# ConverterBoardRev2_3.net
KiCad netlist of a schematic drawn in EAGLE
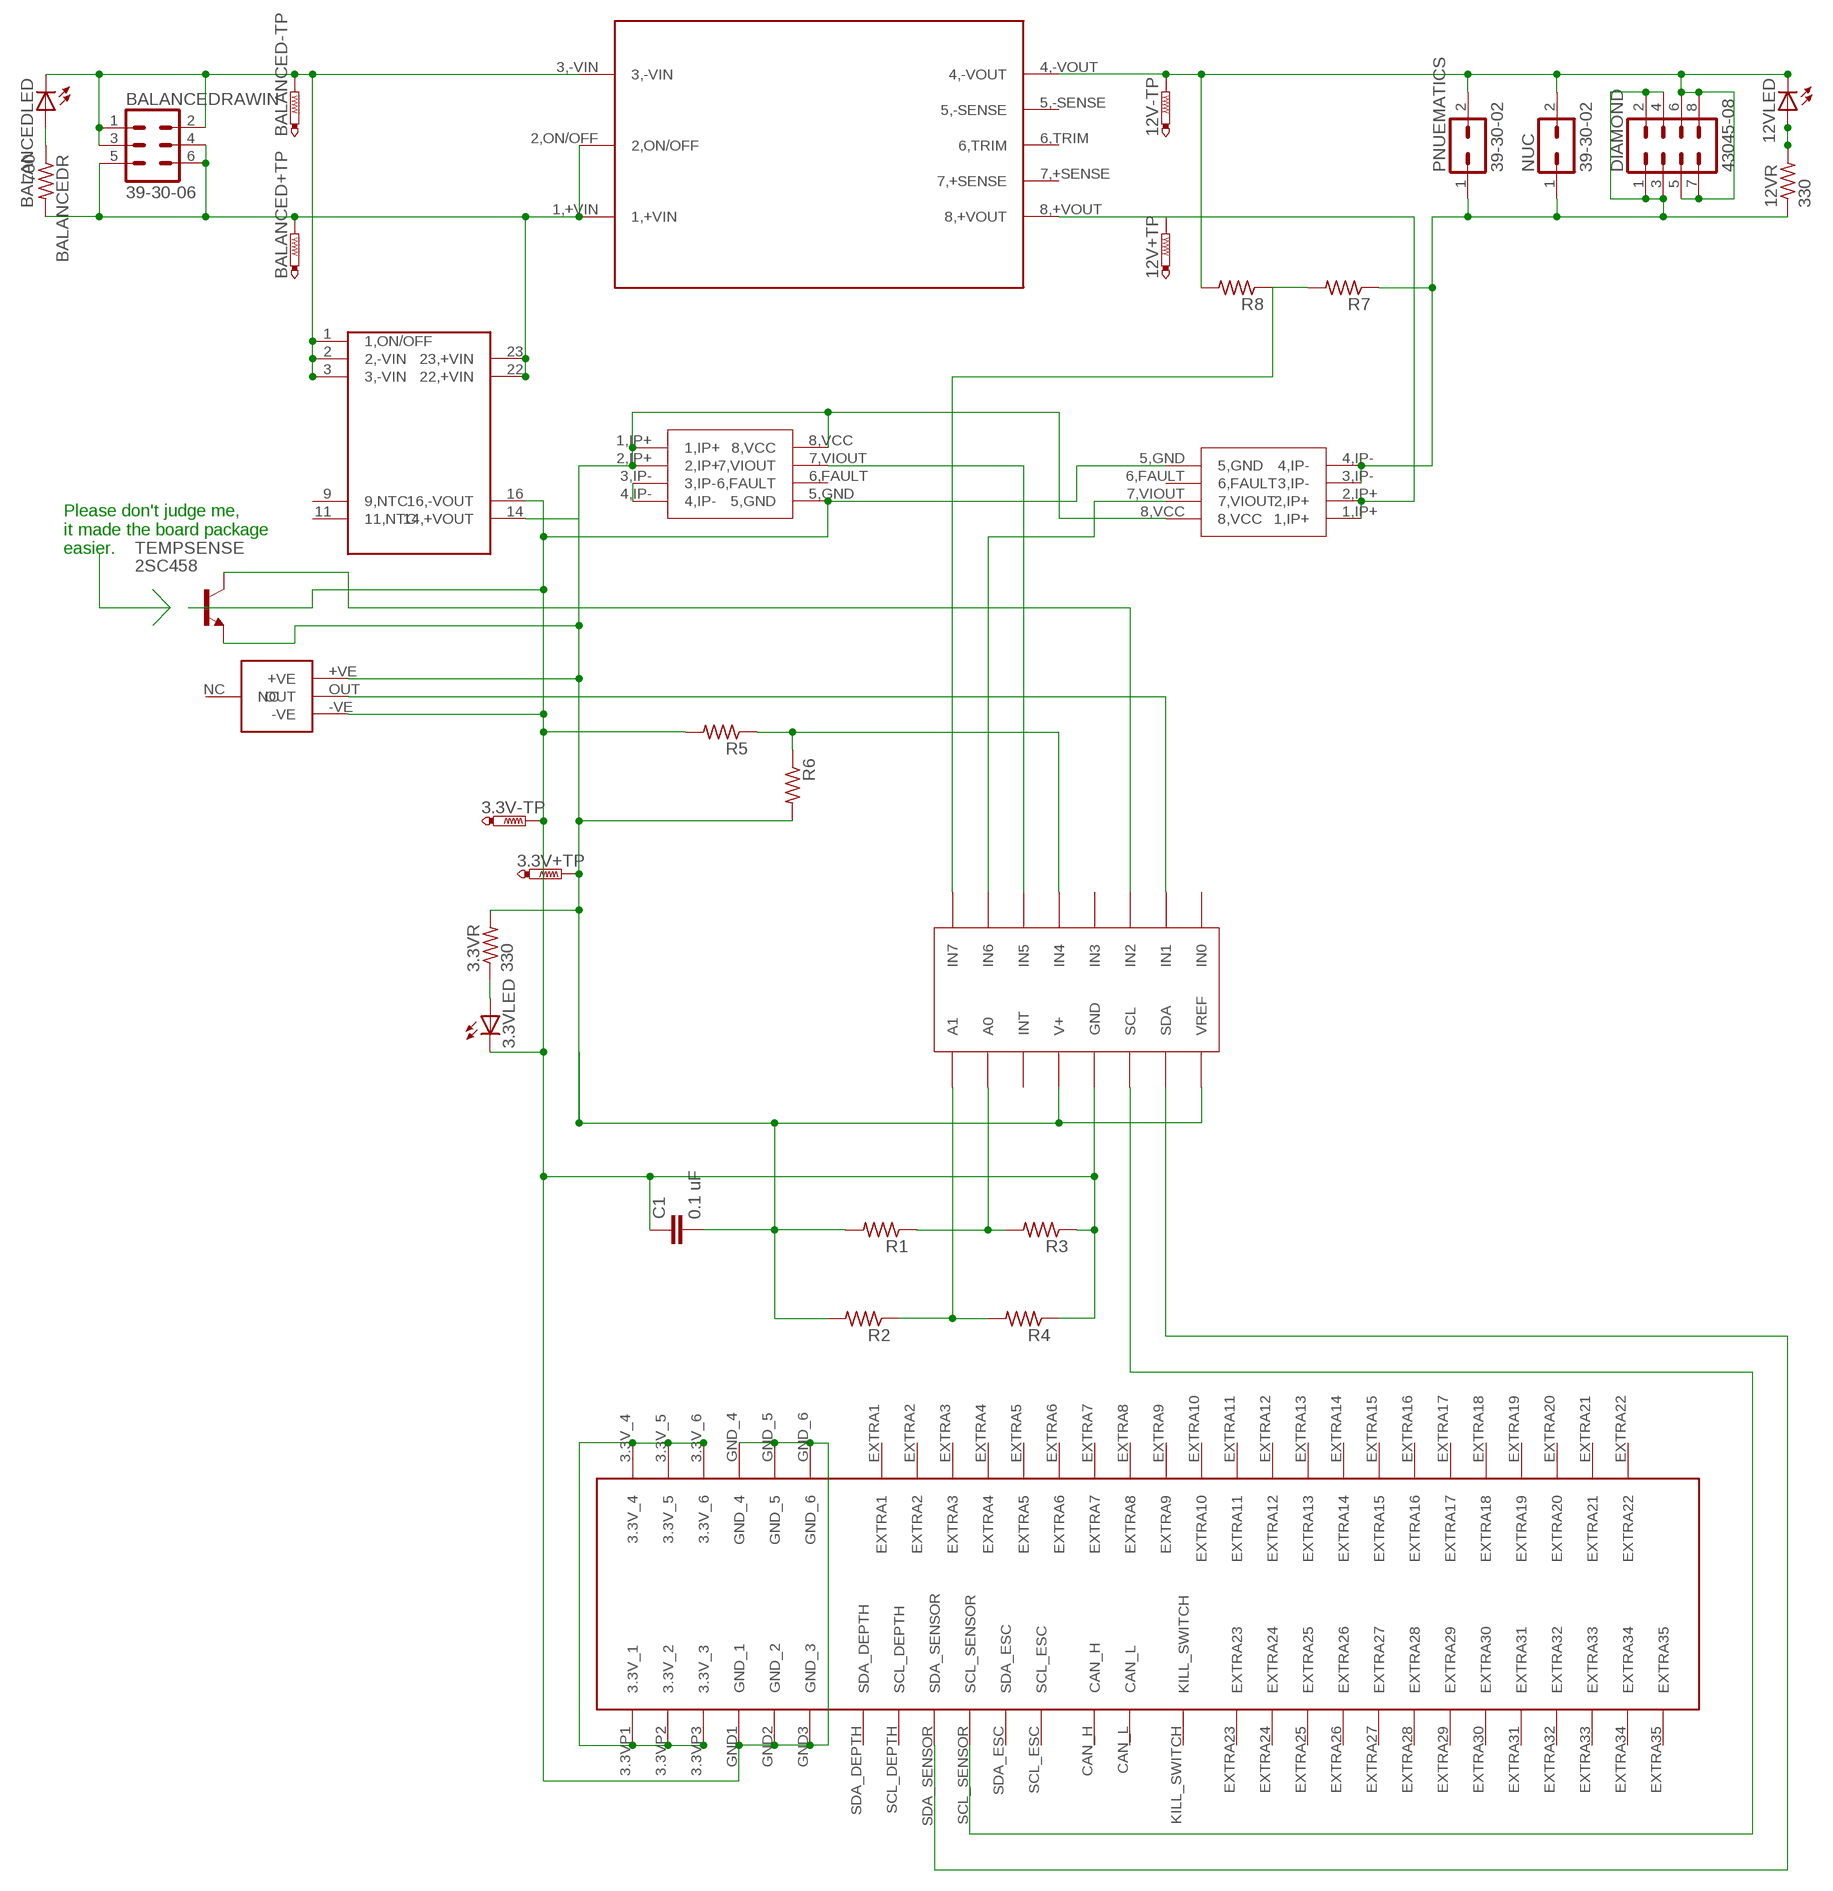
[diagram p0: schematic, sheet 1]

(export (version "E")
  (design (tool "Eeschema 10.0.6"))
  (components
    (comp (ref "3.3V+TP")
      (value "PTR1B1,27")
      (footprint "eagle-import:B1,27")
      (libsource (lib "eagle-import") (part "PTR1B1,27"))
    )
    (comp (ref "3.3V-TP")
      (value "PTR1B1,27")
      (footprint "eagle-import:B1,27")
      (libsource (lib "eagle-import") (part "PTR1B1,27"))
    )
    (comp (ref "3.3VLED")
      (value "LTST-S270GKT")
      (footprint "eagle-import:LTST-S270GKT")
      (libsource (lib "eagle-import") (part "LTST-S270GKT"))
    )
    (comp (ref "3.3VR")
      (value "330")
      (footprint "eagle-import:0204_7")
      (libsource (lib "eagle-import") (part "R-US_0204/7"))
    )
    (comp (ref "3V3CUR")
      (value "CURRENTSENS")
      (footprint "eagle-import:CURRENTSENS")
      (libsource (lib "eagle-import") (part "CURRENTSENS"))
    )
    (comp (ref "12V+TP")
      (value "PTR1B1,27")
      (footprint "eagle-import:B1,27")
      (libsource (lib "eagle-import") (part "PTR1B1,27"))
    )
    (comp (ref "12V-TP")
      (value "PTR1B1,27")
      (footprint "eagle-import:B1,27")
      (libsource (lib "eagle-import") (part "PTR1B1,27"))
    )
    (comp (ref "12VCUR")
      (value "CURRENTSENS")
      (footprint "eagle-import:CURRENTSENS")
      (libsource (lib "eagle-import") (part "CURRENTSENS"))
    )
    (comp (ref "12VLED")
      (value "LTST-S270GKT")
      (footprint "eagle-import:LTST-S270GKT")
      (libsource (lib "eagle-import") (part "LTST-S270GKT"))
    )
    (comp (ref "12VR")
      (value "330")
      (footprint "eagle-import:0204_7")
      (libsource (lib "eagle-import") (part "R-US_0204/7"))
    )
    (comp (ref "BALANCED+TP")
      (value "PTR1B1,27")
      (footprint "eagle-import:B1,27")
      (libsource (lib "eagle-import") (part "PTR1B1,27"))
    )
    (comp (ref "BALANCED-TP")
      (value "PTR1B1,27")
      (footprint "eagle-import:B1,27")
      (libsource (lib "eagle-import") (part "PTR1B1,27"))
    )
    (comp (ref "BALANCEDLED")
      (value "LTST-S270GKT")
      (footprint "eagle-import:LTST-S270GKT")
      (libsource (lib "eagle-import") (part "LTST-S270GKT"))
    )
    (comp (ref "BALANCEDR")
      (value "700")
      (footprint "eagle-import:0204_7")
      (libsource (lib "eagle-import") (part "R-US_0204/7"))
    )
    (comp (ref "BALANCEDRAWIN")
      (value "39-30-06")
      (footprint "eagle-import:39-30-_06_")
      (libsource (lib "eagle-import") (part "39-30-?06?"))
    )
    (comp (ref "C1")
      (value "0.1 uF")
      (footprint "eagle-import:C025-024X044")
      (libsource (lib "eagle-import") (part "C-EU025-024X044"))
    )
    (comp (ref "DIAMOND")
      (value "43045-08")
      (footprint "eagle-import:43045-08")
      (libsource (lib "eagle-import") (part "43045-08"))
    )
    (comp (ref "NUC")
      (value "39-30-02")
      (footprint "eagle-import:39-30-_02_")
      (libsource (lib "eagle-import") (part "39-30-?02?"))
    )
    (comp (ref "PNUEMATICS")
      (value "39-30-02")
      (footprint "eagle-import:39-30-_02_")
      (libsource (lib "eagle-import") (part "39-30-?02?"))
    )
    (comp (ref "R1")
      (value "R-US_0204/7")
      (footprint "eagle-import:0204_7")
      (libsource (lib "eagle-import") (part "R-US_0204/7"))
    )
    (comp (ref "R2")
      (value "R-US_0204/7")
      (footprint "eagle-import:0204_7")
      (libsource (lib "eagle-import") (part "R-US_0204/7"))
    )
    (comp (ref "R3")
      (value "R-US_0204/7")
      (footprint "eagle-import:0204_7")
      (libsource (lib "eagle-import") (part "R-US_0204/7"))
    )
    (comp (ref "R4")
      (value "R-US_0204/7")
      (footprint "eagle-import:0204_7")
      (libsource (lib "eagle-import") (part "R-US_0204/7"))
    )
    (comp (ref "R5")
      (value "R-US_0204/7")
      (footprint "eagle-import:0204_7")
      (libsource (lib "eagle-import") (part "R-US_0204/7"))
    )
    (comp (ref "R6")
      (value "R-US_0204/7")
      (footprint "eagle-import:0204_7")
      (libsource (lib "eagle-import") (part "R-US_0204/7"))
    )
    (comp (ref "R7")
      (value "R-US_0204/7")
      (footprint "eagle-import:0204_7")
      (libsource (lib "eagle-import") (part "R-US_0204/7"))
    )
    (comp (ref "R8")
      (value "R-US_0204/7")
      (footprint "eagle-import:0204_7")
      (libsource (lib "eagle-import") (part "R-US_0204/7"))
    )
    (comp (ref "TEMPSENSE")
      (value "2SC458")
      (footprint "eagle-import:TO92-ECB")
      (libsource (lib "eagle-import") (part "2SC458"))
    )
    (comp (ref "U$1")
      (value "12VCONV")
      (footprint "eagle-import:12VCONV")
      (libsource (lib "eagle-import") (part "12VCONV"))
    )
    (comp (ref "U$2")
      (value "3.3VCONV")
      (footprint "eagle-import:3.3VCONV")
      (libsource (lib "eagle-import") (part "3.3VCONV"))
    )
    (comp (ref "U$3")
      (value "5530843")
      (footprint "eagle-import:5530843-6-BOARDFINGERS")
      (libsource (lib "eagle-import") (part "5530843"))
    )
    (comp (ref "U$6")
      (value "HUMIDITYSENSOR")
      (footprint "eagle-import:HUMIDITYSENSOR")
      (libsource (lib "eagle-import") (part "HUMIDITYSENSOR"))
    )
    (comp (ref "U$8")
      (value "ADC128D818")
      (footprint "eagle-import:TSSOP-16")
      (libsource (lib "eagle-import") (part "ADC128D818"))
    )
  )
  (nets
    (net (code "1") (name "/3.3VBKPLN") (class "Default")
      (node (ref "3V3CUR") (pin "3,IP-") (pinfunction "3,IP-_3,IP-") (pintype "bidirectional"))
      (node (ref "3V3CUR") (pin "4,IP-") (pinfunction "4,IP-_4,IP-") (pintype "bidirectional"))
      (node (ref "U$3") (pin "3.3VP1") (pinfunction "3.3V_1_3.3VP1") (pintype "bidirectional"))
      (node (ref "U$3") (pin "3.3VP2") (pinfunction "3.3V_2_3.3VP2") (pintype "bidirectional"))
      (node (ref "U$3") (pin "3.3VP3") (pinfunction "3.3V_3_3.3VP3") (pintype "bidirectional"))
      (node (ref "U$3") (pin "3.3V_4") (pinfunction "3.3V_4_3.3V_4") (pintype "bidirectional"))
      (node (ref "U$3") (pin "3.3V_5") (pinfunction "3.3V_5_3.3V_5") (pintype "bidirectional"))
      (node (ref "U$3") (pin "3.3V_6") (pinfunction "3.3V_6_3.3V_6") (pintype "bidirectional"))
    )
    (net (code "2") (name "Net-(3.3VLED-A)") (class "Default")
      (node (ref "3.3VLED") (pin "ANODE") (pinfunction "A_ANODE") (pintype "passive"))
      (node (ref "3.3VR") (pin "1") (pinfunction "1_1") (pintype "passive"))
    )
    (net (code "3") (name "Net-(3.3VLED-C)") (class "Default")
      (node (ref "12VCUR") (pin "5,GND") (pinfunction "5,GND_5,GND") (pintype "bidirectional"))
      (node (ref "3.3V-TP") (pin "TP") (pinfunction "TP_TP") (pintype "input"))
      (node (ref "3.3VLED") (pin "CATHODE") (pinfunction "C_CATHODE") (pintype "passive"))
      (node (ref "3V3CUR") (pin "5,GND") (pinfunction "5,GND_5,GND") (pintype "bidirectional"))
      (node (ref "C1") (pin "1") (pinfunction "1_1") (pintype "passive"))
      (node (ref "R3") (pin "1") (pinfunction "1_1") (pintype "passive"))
      (node (ref "R4") (pin "1") (pinfunction "1_1") (pintype "passive"))
      (node (ref "R5") (pin "2") (pinfunction "2_2") (pintype "passive"))
      (node (ref "TEMPSENSE") (pin "B") (pinfunction "B_B") (pintype "passive"))
      (node (ref "U$2") (pin "16") (pinfunction "16,-VOUT_16") (pintype "bidirectional"))
      (node (ref "U$3") (pin "GND1") (pinfunction "GND_1_GND1") (pintype "bidirectional"))
      (node (ref "U$3") (pin "GND2") (pinfunction "GND_2_GND2") (pintype "bidirectional"))
      (node (ref "U$3") (pin "GND3") (pinfunction "GND_3_GND3") (pintype "bidirectional"))
      (node (ref "U$3") (pin "GND_4") (pinfunction "GND_4_GND_4") (pintype "bidirectional"))
      (node (ref "U$3") (pin "GND_5") (pinfunction "GND_5_GND_5") (pintype "bidirectional"))
      (node (ref "U$3") (pin "GND_6") (pinfunction "GND_6_GND_6") (pintype "bidirectional"))
      (node (ref "U$6") (pin "-VE") (pinfunction "-VE_-VE") (pintype "bidirectional"))
      (node (ref "U$8") (pin "GND") (pinfunction "GND_GND") (pintype "bidirectional"))
    )
    (net (code "4") (name "Net-(3V3CUR-Pad7,VIOUT)") (class "Default")
      (node (ref "3V3CUR") (pin "7,VIOUT") (pinfunction "7,VIOUT_7,VIOUT") (pintype "bidirectional"))
      (node (ref "U$8") (pin "IN5") (pinfunction "IN5_IN5") (pintype "bidirectional"))
    )
    (net (code "5") (name "Net-(12VCUR-Pad1,IP+)") (class "Default")
      (node (ref "12VCUR") (pin "1,IP+") (pinfunction "1,IP+_1,IP+") (pintype "bidirectional"))
      (node (ref "12VCUR") (pin "2,IP+") (pinfunction "2,IP+_2,IP+") (pintype "bidirectional"))
      (node (ref "U$1") (pin "8,+VOUT") (pinfunction "8,+VOUT_8,+VOUT") (pintype "bidirectional"))
    )
    (net (code "6") (name "Net-(12VCUR-Pad3,IP-)") (class "Default")
      (node (ref "12VCUR") (pin "3,IP-") (pinfunction "3,IP-_3,IP-") (pintype "bidirectional"))
      (node (ref "12VCUR") (pin "4,IP-") (pinfunction "4,IP-_4,IP-") (pintype "bidirectional"))
      (node (ref "12VR") (pin "1") (pinfunction "1_1") (pintype "passive"))
      (node (ref "DIAMOND") (pin "1") (pinfunction "1_1") (pintype "passive"))
      (node (ref "DIAMOND") (pin "2") (pinfunction "2_2") (pintype "passive"))
      (node (ref "DIAMOND") (pin "3") (pinfunction "3_3") (pintype "passive"))
      (node (ref "DIAMOND") (pin "4") (pinfunction "4_4") (pintype "passive"))
      (node (ref "NUC") (pin "1") (pinfunction "1_1") (pintype "passive"))
      (node (ref "PNUEMATICS") (pin "1") (pinfunction "1_1") (pintype "passive"))
      (node (ref "R7") (pin "1") (pinfunction "1_1") (pintype "passive"))
    )
    (net (code "7") (name "Net-(12VCUR-Pad7,VIOUT)") (class "Default")
      (node (ref "12VCUR") (pin "7,VIOUT") (pinfunction "7,VIOUT_7,VIOUT") (pintype "bidirectional"))
      (node (ref "U$8") (pin "IN6") (pinfunction "IN6_IN6") (pintype "bidirectional"))
    )
    (net (code "8") (name "Net-(12VLED-A)") (class "Default")
      (node (ref "12VLED") (pin "ANODE") (pinfunction "A_ANODE") (pintype "passive"))
      (node (ref "12VR") (pin "2") (pinfunction "2_2") (pintype "passive"))
    )
    (net (code "9") (name "Net-(12VLED-C)") (class "Default")
      (node (ref "12V-TP") (pin "TP") (pinfunction "TP_TP") (pintype "input"))
      (node (ref "12VLED") (pin "CATHODE") (pinfunction "C_CATHODE") (pintype "passive"))
      (node (ref "DIAMOND") (pin "5") (pinfunction "5_5") (pintype "passive"))
      (node (ref "DIAMOND") (pin "6") (pinfunction "6_6") (pintype "passive"))
      (node (ref "DIAMOND") (pin "7") (pinfunction "7_7") (pintype "passive"))
      (node (ref "DIAMOND") (pin "8") (pinfunction "8_8") (pintype "passive"))
      (node (ref "NUC") (pin "2") (pinfunction "2_2") (pintype "passive"))
      (node (ref "PNUEMATICS") (pin "2") (pinfunction "2_2") (pintype "passive"))
      (node (ref "R8") (pin "2") (pinfunction "2_2") (pintype "passive"))
      (node (ref "U$1") (pin "4,-VOUT") (pinfunction "4,-VOUT_4,-VOUT") (pintype "bidirectional"))
    )
    (net (code "10") (name "Net-(BALANCEDLED-A)") (class "Default")
      (node (ref "BALANCEDLED") (pin "ANODE") (pinfunction "A_ANODE") (pintype "passive"))
      (node (ref "BALANCEDR") (pin "1") (pinfunction "1_1") (pintype "passive"))
    )
    (net (code "11") (name "Net-(BALANCEDLED-C)") (class "Default")
      (node (ref "BALANCED-TP") (pin "TP") (pinfunction "TP_TP") (pintype "input"))
      (node (ref "BALANCEDLED") (pin "CATHODE") (pinfunction "C_CATHODE") (pintype "passive"))
      (node (ref "BALANCEDRAWIN") (pin "1") (pinfunction "1_1") (pintype "passive"))
      (node (ref "BALANCEDRAWIN") (pin "2") (pinfunction "2_2") (pintype "passive"))
      (node (ref "BALANCEDRAWIN") (pin "3") (pinfunction "3_3") (pintype "passive"))
      (node (ref "U$1") (pin "3,-VIN") (pinfunction "3,-VIN_3,-VIN") (pintype "bidirectional"))
      (node (ref "U$2") (pin "1") (pinfunction "1,ON/OFF_1") (pintype "bidirectional"))
      (node (ref "U$2") (pin "2") (pinfunction "2,-VIN_2") (pintype "bidirectional"))
      (node (ref "U$2") (pin "3") (pinfunction "3,-VIN_3") (pintype "bidirectional"))
    )
    (net (code "12") (name "Net-(R1-Pad1)") (class "Default")
      (node (ref "R1") (pin "1") (pinfunction "1_1") (pintype "passive"))
      (node (ref "R3") (pin "2") (pinfunction "2_2") (pintype "passive"))
      (node (ref "U$8") (pin "A0") (pinfunction "A0_A0") (pintype "bidirectional"))
    )
    (net (code "13") (name "Net-(R2-Pad1)") (class "Default")
      (node (ref "R2") (pin "1") (pinfunction "1_1") (pintype "passive"))
      (node (ref "R4") (pin "2") (pinfunction "2_2") (pintype "passive"))
      (node (ref "U$8") (pin "A1") (pinfunction "A1_A1") (pintype "bidirectional"))
    )
    (net (code "14") (name "Net-(R5-Pad1)") (class "Default")
      (node (ref "R5") (pin "1") (pinfunction "1_1") (pintype "passive"))
      (node (ref "R6") (pin "1") (pinfunction "1_1") (pintype "passive"))
      (node (ref "U$8") (pin "IN4") (pinfunction "IN4_IN4") (pintype "bidirectional"))
    )
    (net (code "15") (name "Net-(R7-Pad2)") (class "Default")
      (node (ref "R7") (pin "2") (pinfunction "2_2") (pintype "passive"))
      (node (ref "R8") (pin "1") (pinfunction "1_1") (pintype "passive"))
      (node (ref "U$8") (pin "IN7") (pinfunction "IN7_IN7") (pintype "bidirectional"))
    )
    (net (code "16") (name "Net-(TEMPSENSE-PadC)") (class "Default")
      (node (ref "TEMPSENSE") (pin "C") (pinfunction "C_C") (pintype "passive"))
      (node (ref "U$8") (pin "IN2") (pinfunction "IN2_IN2") (pintype "bidirectional"))
    )
    (net (code "17") (name "Net-(U$2-14,+VOUT)") (class "Default")
      (node (ref "12VCUR") (pin "8,VCC") (pinfunction "8,VCC_8,VCC") (pintype "bidirectional"))
      (node (ref "3.3V+TP") (pin "TP") (pinfunction "TP_TP") (pintype "input"))
      (node (ref "3.3VR") (pin "2") (pinfunction "2_2") (pintype "passive"))
      (node (ref "3V3CUR") (pin "1,IP+") (pinfunction "1,IP+_1,IP+") (pintype "bidirectional"))
      (node (ref "3V3CUR") (pin "2,IP+") (pinfunction "2,IP+_2,IP+") (pintype "bidirectional"))
      (node (ref "3V3CUR") (pin "8,VCC") (pinfunction "8,VCC_8,VCC") (pintype "bidirectional"))
      (node (ref "C1") (pin "2") (pinfunction "2_2") (pintype "passive"))
      (node (ref "R1") (pin "2") (pinfunction "2_2") (pintype "passive"))
      (node (ref "R2") (pin "2") (pinfunction "2_2") (pintype "passive"))
      (node (ref "R6") (pin "2") (pinfunction "2_2") (pintype "passive"))
      (node (ref "TEMPSENSE") (pin "E") (pinfunction "E_E") (pintype "passive"))
      (node (ref "U$2") (pin "14") (pinfunction "14,+VOUT_14") (pintype "bidirectional"))
      (node (ref "U$6") (pin "+VE") (pinfunction "+VE_+VE") (pintype "bidirectional"))
      (node (ref "U$8") (pin "V+") (pinfunction "V+_V+") (pintype "bidirectional"))
      (node (ref "U$8") (pin "VREF") (pinfunction "VREF_VREF") (pintype "bidirectional"))
    )
    (net (code "18") (name "Net-(U$2-22,+VIN)") (class "Default")
      (node (ref "BALANCED+TP") (pin "TP") (pinfunction "TP_TP") (pintype "input"))
      (node (ref "BALANCEDR") (pin "2") (pinfunction "2_2") (pintype "passive"))
      (node (ref "BALANCEDRAWIN") (pin "4") (pinfunction "4_4") (pintype "passive"))
      (node (ref "BALANCEDRAWIN") (pin "5") (pinfunction "5_5") (pintype "passive"))
      (node (ref "BALANCEDRAWIN") (pin "6") (pinfunction "6_6") (pintype "passive"))
      (node (ref "U$1") (pin "1,+VIN") (pinfunction "1,+VIN_1,+VIN") (pintype "bidirectional"))
      (node (ref "U$1") (pin "2,ON/OFF") (pinfunction "2,ON/OFF_2,ON/OFF") (pintype "bidirectional"))
      (node (ref "U$2") (pin "22") (pinfunction "22,+VIN_22") (pintype "bidirectional"))
      (node (ref "U$2") (pin "23") (pinfunction "23,+VIN_23") (pintype "bidirectional"))
    )
    (net (code "19") (name "Net-(U$3-PadSCL_SENSOR)") (class "Default")
      (node (ref "U$3") (pin "SCL_SENSOR") (pinfunction "SCL_SENSOR_SCL_SENSOR") (pintype "bidirectional"))
      (node (ref "U$8") (pin "SCL") (pinfunction "SCL_SCL") (pintype "bidirectional"))
    )
    (net (code "20") (name "Net-(U$3-PadSDA_SENSOR)") (class "Default")
      (node (ref "U$3") (pin "SDA_SENSOR") (pinfunction "SDA_SENSOR_SDA_SENSOR") (pintype "bidirectional"))
      (node (ref "U$8") (pin "SDA") (pinfunction "SDA_SDA") (pintype "bidirectional"))
    )
    (net (code "21") (name "Net-(U$6-PadOUT)") (class "Default")
      (node (ref "U$6") (pin "OUT") (pinfunction "OUT_OUT") (pintype "bidirectional"))
      (node (ref "U$8") (pin "IN1") (pinfunction "IN1_IN1") (pintype "bidirectional"))
    )
    (net (code "22") (name "unconnected-(3V3CUR-Pad6,FAULT)") (class "Default")
      (node (ref "3V3CUR") (pin "6,FAULT") (pinfunction "6,FAULT_6,FAULT") (pintype "bidirectional"))
    )
    (net (code "23") (name "unconnected-(12V+TP-PadTP)") (class "Default")
      (node (ref "12V+TP") (pin "TP") (pinfunction "TP_TP") (pintype "input"))
    )
    (net (code "24") (name "unconnected-(12VCUR-Pad6,FAULT)") (class "Default")
      (node (ref "12VCUR") (pin "6,FAULT") (pinfunction "6,FAULT_6,FAULT") (pintype "bidirectional"))
    )
    (net (code "25") (name "unconnected-(U$1-Pad5,-SENSE)") (class "Default")
      (node (ref "U$1") (pin "5,-SENSE") (pinfunction "5,-SENSE_5,-SENSE") (pintype "bidirectional"))
    )
    (net (code "26") (name "unconnected-(U$1-Pad6,TRIM)") (class "Default")
      (node (ref "U$1") (pin "6,TRIM") (pinfunction "6,TRIM_6,TRIM") (pintype "bidirectional"))
    )
    (net (code "27") (name "unconnected-(U$1-Pad7,+SENSE)") (class "Default")
      (node (ref "U$1") (pin "7,+SENSE") (pinfunction "7,+SENSE_7,+SENSE") (pintype "bidirectional"))
    )
    (net (code "28") (name "unconnected-(U$2-9,NTC-Pad9)") (class "Default")
      (node (ref "U$2") (pin "9") (pinfunction "9,NTC_9") (pintype "bidirectional"))
    )
    (net (code "29") (name "unconnected-(U$2-11,NTC-Pad11)") (class "Default")
      (node (ref "U$2") (pin "11") (pinfunction "11,NTC_11") (pintype "bidirectional"))
    )
    (net (code "30") (name "unconnected-(U$3-PadCAN_H)") (class "Default")
      (node (ref "U$3") (pin "CAN_H") (pinfunction "CAN_H_CAN_H") (pintype "bidirectional"))
    )
    (net (code "31") (name "unconnected-(U$3-PadCAN_L)") (class "Default")
      (node (ref "U$3") (pin "CAN_L") (pinfunction "CAN_L_CAN_L") (pintype "bidirectional"))
    )
    (net (code "32") (name "unconnected-(U$3-PadEXTRA1)") (class "Default")
      (node (ref "U$3") (pin "EXTRA1") (pinfunction "EXTRA1_EXTRA1") (pintype "bidirectional"))
    )
    (net (code "33") (name "unconnected-(U$3-PadEXTRA2)") (class "Default")
      (node (ref "U$3") (pin "EXTRA2") (pinfunction "EXTRA2_EXTRA2") (pintype "bidirectional"))
    )
    (net (code "34") (name "unconnected-(U$3-PadEXTRA3)") (class "Default")
      (node (ref "U$3") (pin "EXTRA3") (pinfunction "EXTRA3_EXTRA3") (pintype "bidirectional"))
    )
    (net (code "35") (name "unconnected-(U$3-PadEXTRA4)") (class "Default")
      (node (ref "U$3") (pin "EXTRA4") (pinfunction "EXTRA4_EXTRA4") (pintype "bidirectional"))
    )
    (net (code "36") (name "unconnected-(U$3-PadEXTRA5)") (class "Default")
      (node (ref "U$3") (pin "EXTRA5") (pinfunction "EXTRA5_EXTRA5") (pintype "bidirectional"))
    )
    (net (code "37") (name "unconnected-(U$3-PadEXTRA6)") (class "Default")
      (node (ref "U$3") (pin "EXTRA6") (pinfunction "EXTRA6_EXTRA6") (pintype "bidirectional"))
    )
    (net (code "38") (name "unconnected-(U$3-PadEXTRA7)") (class "Default")
      (node (ref "U$3") (pin "EXTRA7") (pinfunction "EXTRA7_EXTRA7") (pintype "bidirectional"))
    )
    (net (code "39") (name "unconnected-(U$3-PadEXTRA8)") (class "Default")
      (node (ref "U$3") (pin "EXTRA8") (pinfunction "EXTRA8_EXTRA8") (pintype "bidirectional"))
    )
    (net (code "40") (name "unconnected-(U$3-PadEXTRA9)") (class "Default")
      (node (ref "U$3") (pin "EXTRA9") (pinfunction "EXTRA9_EXTRA9") (pintype "bidirectional"))
    )
    (net (code "41") (name "unconnected-(U$3-PadEXTRA10)") (class "Default")
      (node (ref "U$3") (pin "EXTRA10") (pinfunction "EXTRA10_EXTRA10") (pintype "bidirectional"))
    )
    (net (code "42") (name "unconnected-(U$3-PadEXTRA11)") (class "Default")
      (node (ref "U$3") (pin "EXTRA11") (pinfunction "EXTRA11_EXTRA11") (pintype "bidirectional"))
    )
    (net (code "43") (name "unconnected-(U$3-PadEXTRA12)") (class "Default")
      (node (ref "U$3") (pin "EXTRA12") (pinfunction "EXTRA12_EXTRA12") (pintype "bidirectional"))
    )
    (net (code "44") (name "unconnected-(U$3-PadEXTRA13)") (class "Default")
      (node (ref "U$3") (pin "EXTRA13") (pinfunction "EXTRA13_EXTRA13") (pintype "bidirectional"))
    )
    (net (code "45") (name "unconnected-(U$3-PadEXTRA14)") (class "Default")
      (node (ref "U$3") (pin "EXTRA14") (pinfunction "EXTRA14_EXTRA14") (pintype "bidirectional"))
    )
    (net (code "46") (name "unconnected-(U$3-PadEXTRA15)") (class "Default")
      (node (ref "U$3") (pin "EXTRA15") (pinfunction "EXTRA15_EXTRA15") (pintype "bidirectional"))
    )
    (net (code "47") (name "unconnected-(U$3-PadEXTRA16)") (class "Default")
      (node (ref "U$3") (pin "EXTRA16") (pinfunction "EXTRA16_EXTRA16") (pintype "bidirectional"))
    )
    (net (code "48") (name "unconnected-(U$3-PadEXTRA17)") (class "Default")
      (node (ref "U$3") (pin "EXTRA17") (pinfunction "EXTRA17_EXTRA17") (pintype "bidirectional"))
    )
    (net (code "49") (name "unconnected-(U$3-PadEXTRA18)") (class "Default")
      (node (ref "U$3") (pin "EXTRA18") (pinfunction "EXTRA18_EXTRA18") (pintype "bidirectional"))
    )
    (net (code "50") (name "unconnected-(U$3-PadEXTRA19)") (class "Default")
      (node (ref "U$3") (pin "EXTRA19") (pinfunction "EXTRA19_EXTRA19") (pintype "bidirectional"))
    )
    (net (code "51") (name "unconnected-(U$3-PadEXTRA20)") (class "Default")
      (node (ref "U$3") (pin "EXTRA20") (pinfunction "EXTRA20_EXTRA20") (pintype "bidirectional"))
    )
    (net (code "52") (name "unconnected-(U$3-PadEXTRA21)") (class "Default")
      (node (ref "U$3") (pin "EXTRA21") (pinfunction "EXTRA21_EXTRA21") (pintype "bidirectional"))
    )
    (net (code "53") (name "unconnected-(U$3-PadEXTRA22)") (class "Default")
      (node (ref "U$3") (pin "EXTRA22") (pinfunction "EXTRA22_EXTRA22") (pintype "bidirectional"))
    )
    (net (code "54") (name "unconnected-(U$3-PadEXTRA23)") (class "Default")
      (node (ref "U$3") (pin "EXTRA23") (pinfunction "EXTRA23_EXTRA23") (pintype "bidirectional"))
    )
    (net (code "55") (name "unconnected-(U$3-PadEXTRA24)") (class "Default")
      (node (ref "U$3") (pin "EXTRA24") (pinfunction "EXTRA24_EXTRA24") (pintype "bidirectional"))
    )
    (net (code "56") (name "unconnected-(U$3-PadEXTRA25)") (class "Default")
      (node (ref "U$3") (pin "EXTRA25") (pinfunction "EXTRA25_EXTRA25") (pintype "bidirectional"))
    )
    (net (code "57") (name "unconnected-(U$3-PadEXTRA26)") (class "Default")
      (node (ref "U$3") (pin "EXTRA26") (pinfunction "EXTRA26_EXTRA26") (pintype "bidirectional"))
    )
    (net (code "58") (name "unconnected-(U$3-PadEXTRA27)") (class "Default")
      (node (ref "U$3") (pin "EXTRA27") (pinfunction "EXTRA27_EXTRA27") (pintype "bidirectional"))
    )
    (net (code "59") (name "unconnected-(U$3-PadEXTRA28)") (class "Default")
      (node (ref "U$3") (pin "EXTRA28") (pinfunction "EXTRA28_EXTRA28") (pintype "bidirectional"))
    )
    (net (code "60") (name "unconnected-(U$3-PadEXTRA29)") (class "Default")
      (node (ref "U$3") (pin "EXTRA29") (pinfunction "EXTRA29_EXTRA29") (pintype "bidirectional"))
    )
    (net (code "61") (name "unconnected-(U$3-PadEXTRA30)") (class "Default")
      (node (ref "U$3") (pin "EXTRA30") (pinfunction "EXTRA30_EXTRA30") (pintype "bidirectional"))
    )
    (net (code "62") (name "unconnected-(U$3-PadEXTRA31)") (class "Default")
      (node (ref "U$3") (pin "EXTRA31") (pinfunction "EXTRA31_EXTRA31") (pintype "bidirectional"))
    )
    (net (code "63") (name "unconnected-(U$3-PadEXTRA32)") (class "Default")
      (node (ref "U$3") (pin "EXTRA32") (pinfunction "EXTRA32_EXTRA32") (pintype "bidirectional"))
    )
    (net (code "64") (name "unconnected-(U$3-PadEXTRA33)") (class "Default")
      (node (ref "U$3") (pin "EXTRA33") (pinfunction "EXTRA33_EXTRA33") (pintype "bidirectional"))
    )
    (net (code "65") (name "unconnected-(U$3-PadEXTRA34)") (class "Default")
      (node (ref "U$3") (pin "EXTRA34") (pinfunction "EXTRA34_EXTRA34") (pintype "bidirectional"))
    )
    (net (code "66") (name "unconnected-(U$3-PadEXTRA35)") (class "Default")
      (node (ref "U$3") (pin "EXTRA35") (pinfunction "EXTRA35_EXTRA35") (pintype "bidirectional"))
    )
    (net (code "67") (name "unconnected-(U$3-PadKILL_SWITCH)") (class "Default")
      (node (ref "U$3") (pin "KILL_SWITCH") (pinfunction "KILL_SWITCH_KILL_SWITCH") (pintype "bidirectional"))
    )
    (net (code "68") (name "unconnected-(U$3-PadSCL_DEPTH)") (class "Default")
      (node (ref "U$3") (pin "SCL_DEPTH") (pinfunction "SCL_DEPTH_SCL_DEPTH") (pintype "bidirectional"))
    )
    (net (code "69") (name "unconnected-(U$3-PadSCL_ESC)") (class "Default")
      (node (ref "U$3") (pin "SCL_ESC") (pinfunction "SCL_ESC_SCL_ESC") (pintype "bidirectional"))
    )
    (net (code "70") (name "unconnected-(U$3-PadSDA_DEPTH)") (class "Default")
      (node (ref "U$3") (pin "SDA_DEPTH") (pinfunction "SDA_DEPTH_SDA_DEPTH") (pintype "bidirectional"))
    )
    (net (code "71") (name "unconnected-(U$3-PadSDA_ESC)") (class "Default")
      (node (ref "U$3") (pin "SDA_ESC") (pinfunction "SDA_ESC_SDA_ESC") (pintype "bidirectional"))
    )
    (net (code "72") (name "unconnected-(U$6-PadNC)") (class "Default")
      (node (ref "U$6") (pin "NC") (pinfunction "NC_NC") (pintype "bidirectional"))
    )
    (net (code "73") (name "unconnected-(U$8-PadIN0)") (class "Default")
      (node (ref "U$8") (pin "IN0") (pinfunction "IN0_IN0") (pintype "bidirectional"))
    )
    (net (code "74") (name "unconnected-(U$8-PadIN3)") (class "Default")
      (node (ref "U$8") (pin "IN3") (pinfunction "IN3_IN3") (pintype "bidirectional"))
    )
    (net (code "75") (name "unconnected-(U$8-PadINT)") (class "Default")
      (node (ref "U$8") (pin "INT") (pinfunction "INT_INT") (pintype "bidirectional"))
    )
  )
)
